# assgn1schematic.net
KiCad netlist of a schematic drawn in EAGLE
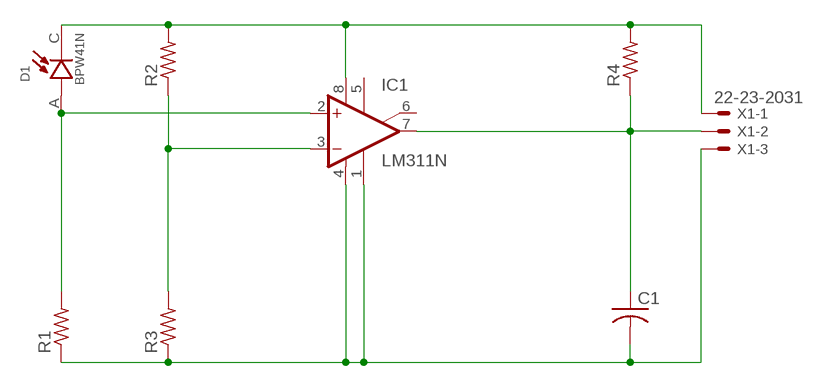
[diagram p0: schematic, sheet 1]

(export (version "E")
  (design (tool "Eeschema 10.0.6"))
  (components
    (comp (ref "C1")
      (value "C-US025-024X044")
      (footprint "eagle-import:C025-024X044")
      (libsource (lib "eagle-import") (part "C-US025-024X044"))
    )
    (comp (ref "D1")
      (value "BPW41N")
      (footprint "eagle-import:DIO_BPW41N")
      (fields (field (name "MF") "Vishay Semiconductor Opto Division"))
      (libsource (lib "eagle-import") (part "BPW41N"))
    )
    (comp (ref "IC1")
      (value "LM311N")
      (footprint "eagle-import:DIL08")
      (libsource (lib "eagle-import") (part "LM311N"))
    )
    (comp (ref "R1")
      (value "R-US_0204/5")
      (footprint "eagle-import:0204_5")
      (libsource (lib "eagle-import") (part "R-US_0204/5"))
    )
    (comp (ref "R2")
      (value "R-US_0204/5")
      (footprint "eagle-import:0204_5")
      (libsource (lib "eagle-import") (part "R-US_0204/5"))
    )
    (comp (ref "R3")
      (value "R-US_0204/5")
      (footprint "eagle-import:0204_5")
      (libsource (lib "eagle-import") (part "R-US_0204/5"))
    )
    (comp (ref "R4")
      (value "R-US_0204/5")
      (footprint "eagle-import:0204_5")
      (libsource (lib "eagle-import") (part "R-US_0204/5"))
    )
    (comp (ref "X1")
      (value "22-23-2031")
      (footprint "eagle-import:22-23-2031")
      (fields (field (name "MF") "MOLEX"))
      (libsource (lib "eagle-import") (part "22-23-2031"))
    )
  )
  (nets
    (net (code "1") (name "Net-(IC1-+IN)") (class "Default")
      (node (ref "D1") (pin "A") (pinfunction "A_A") (pintype "passive"))
      (node (ref "IC1") (pin "2") (pinfunction "+IN_2") (pintype "input"))
      (node (ref "R1") (pin "2") (pinfunction "2_2") (pintype "passive"))
    )
    (net (code "2") (name "Net-(IC1--IN)") (class "Default")
      (node (ref "IC1") (pin "3") (pinfunction "-IN_3") (pintype "input"))
      (node (ref "R2") (pin "1") (pinfunction "1_1") (pintype "passive"))
      (node (ref "R3") (pin "2") (pinfunction "2_2") (pintype "passive"))
    )
    (net (code "3") (name "Net-(IC1-GND)") (class "Default")
      (node (ref "C1") (pin "2") (pinfunction "2_2") (pintype "passive"))
      (node (ref "IC1") (pin "1") (pinfunction "GND_1") (pintype "passive"))
      (node (ref "IC1") (pin "4") (pinfunction "V-_4") (pintype "power_in"))
      (node (ref "R1") (pin "1") (pinfunction "1_1") (pintype "passive"))
      (node (ref "R3") (pin "1") (pinfunction "1_1") (pintype "passive"))
      (node (ref "X1") (pin "3") (pinfunction "S_3") (pintype "passive"))
    )
    (net (code "4") (name "Net-(IC1-OUT)") (class "Default")
      (node (ref "C1") (pin "1") (pinfunction "1_1") (pintype "passive"))
      (node (ref "IC1") (pin "7") (pinfunction "OUT_7") (pintype "output"))
      (node (ref "R4") (pin "1") (pinfunction "1_1") (pintype "passive"))
      (node (ref "X1") (pin "2") (pinfunction "S_2") (pintype "passive"))
    )
    (net (code "5") (name "Net-(IC1-V+)") (class "Default")
      (node (ref "D1") (pin "C") (pinfunction "C_C") (pintype "passive"))
      (node (ref "IC1") (pin "8") (pinfunction "V+_8") (pintype "power_in"))
      (node (ref "R2") (pin "2") (pinfunction "2_2") (pintype "passive"))
      (node (ref "R4") (pin "2") (pinfunction "2_2") (pintype "passive"))
      (node (ref "X1") (pin "1") (pinfunction "S_1") (pintype "passive"))
    )
    (net (code "6") (name "unconnected-(IC1-ON-Pad5)") (class "Default")
      (node (ref "IC1") (pin "5") (pinfunction "ON_5") (pintype "passive"))
    )
    (net (code "7") (name "unconnected-(IC1-ON{slash}STR-Pad6)") (class "Default")
      (node (ref "IC1") (pin "6") (pinfunction "ON/STR_6") (pintype "passive"))
    )
  )
)
